# Expression_Pedal.net
KiCad netlist of a schematic drawn in Altium Designer
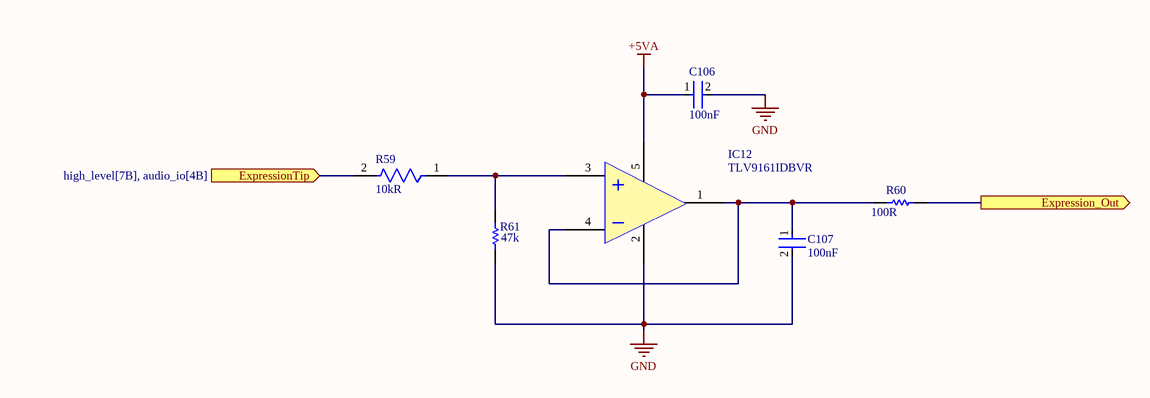
[diagram p0: Expression_Pedal.SchDoc]

(export (version "E")
  (design (tool "Eeschema 10.0.6"))
  (components
    (comp (ref "C106")
      (value "GRM033C71C104ME14J")
      (footprint "FP-GRM033-0_03-IPC_C")
      (description "Chip Multilayer Ceramic Capacitors for General Purpose, 0201, 0.10uF, X7S, 22%, 20%, 16V")
      (fields (field (name "TOLERANCE") "20%") (field (name "CAPACITANCE") "100nF"))
      (libsource (lib "Altium Content Vault") (part "b4654b650e69147ec39a6b967a45e02"))
    )
    (comp (ref "C107")
      (value "GRM033C71C104ME14J")
      (footprint "FP-GRM033-0_03-IPC_C")
      (description "Chip Multilayer Ceramic Capacitors for General Purpose, 0201, 0.10uF, X7S, 22%, 20%, 16V")
      (fields (field (name "TOLERANCE") "20%") (field (name "CAPACITANCE") "100nF"))
      (libsource (lib "Altium Content Vault") (part "b4654b650e69147ec39a6b967a45e02"))
    )
    (comp (ref "IC12")
      (value "TLV9161IDBVR")
      (footprint "SOT95P280X145-5N")
      (description "Integrated Circuit")
      (fields (field (name "MOUSER PART NUMBER") "595-TLV9161IDBVR"))
      (libsource (lib "audio_dev_pcb") (part "TLV9161IDBVR"))
    )
    (comp (ref "R59")
      (value "RC0402FR-1310KL")
      (footprint "FP-RC0402-0_4-IPC_A")
      (description "RESISTOR 0402 10K 1%")
      (fields (field (name "RESISTANCE") "10kR") (field (name "TOLERANCE") "1%"))
      (libsource (lib "Altium Content Vault") (part "1029c3af85768c4190bb7ad29bc67b5"))
    )
    (comp (ref "R60")
      (value "RC0402JR-07100RL")
      (footprint "RESC1005X40X25NL05T10")
      (fields (field (name "MANUFACTURER") "Yageo / Phycomp") (field (name "RESISTANCE") "100R"))
      (libsource (lib "Altium Content Vault") (part "RES"))
    )
    (comp (ref "R61")
      (value "RC0402JR-0747KL")
      (footprint "RESC1005X40X25LL05T10")
      (fields (field (name "MANUFACTURER") "Yageo / Phycomp") (field (name "RESISTANCE") "47k"))
      (libsource (lib "Altium Content Vault") (part "RES"))
    )
  )
  (nets
    (net (code "1") (name "+5VA") (class "Default")
      (node (ref "C106") (pin "1") (pinfunction "1_1") (pintype "passive"))
      (node (ref "IC12") (pin "5") (pinfunction "V+_5") (pintype "passive"))
    )
    (net (code "2") (name "/ExpressionTip") (class "Default")
      (node (ref "R59") (pin "2") (pinfunction "2_2") (pintype "passive"))
    )
    (net (code "3") (name "/Expression_Out") (class "Default")
      (node (ref "R60") (pin "2") (pinfunction "2_2") (pintype "passive"))
    )
    (net (code "4") (name "GND") (class "Default")
      (node (ref "C106") (pin "2") (pinfunction "2_2") (pintype "passive"))
      (node (ref "C107") (pin "2") (pinfunction "2_2") (pintype "passive"))
      (node (ref "IC12") (pin "2") (pinfunction "V-_2") (pintype "passive"))
      (node (ref "R61") (pin "1") (pinfunction "1_1") (pintype "passive"))
    )
    (net (code "5") (name "Net-(IC12-IN+)") (class "Default")
      (node (ref "IC12") (pin "3") (pinfunction "IN+_3") (pintype "passive"))
      (node (ref "R59") (pin "1") (pinfunction "1_1") (pintype "passive"))
      (node (ref "R61") (pin "2") (pinfunction "2_2") (pintype "passive"))
    )
    (net (code "6") (name "Net-(IC12-IN-)") (class "Default")
      (node (ref "C107") (pin "1") (pinfunction "1_1") (pintype "passive"))
      (node (ref "IC12") (pin "1") (pinfunction "OUT_1") (pintype "passive"))
      (node (ref "IC12") (pin "4") (pinfunction "IN-_4") (pintype "passive"))
      (node (ref "R60") (pin "1") (pinfunction "1_1") (pintype "passive"))
    )
  )
)
